# TSOC_GROVEY_ONE.net
KiCad netlist of a schematic drawn in EAGLE
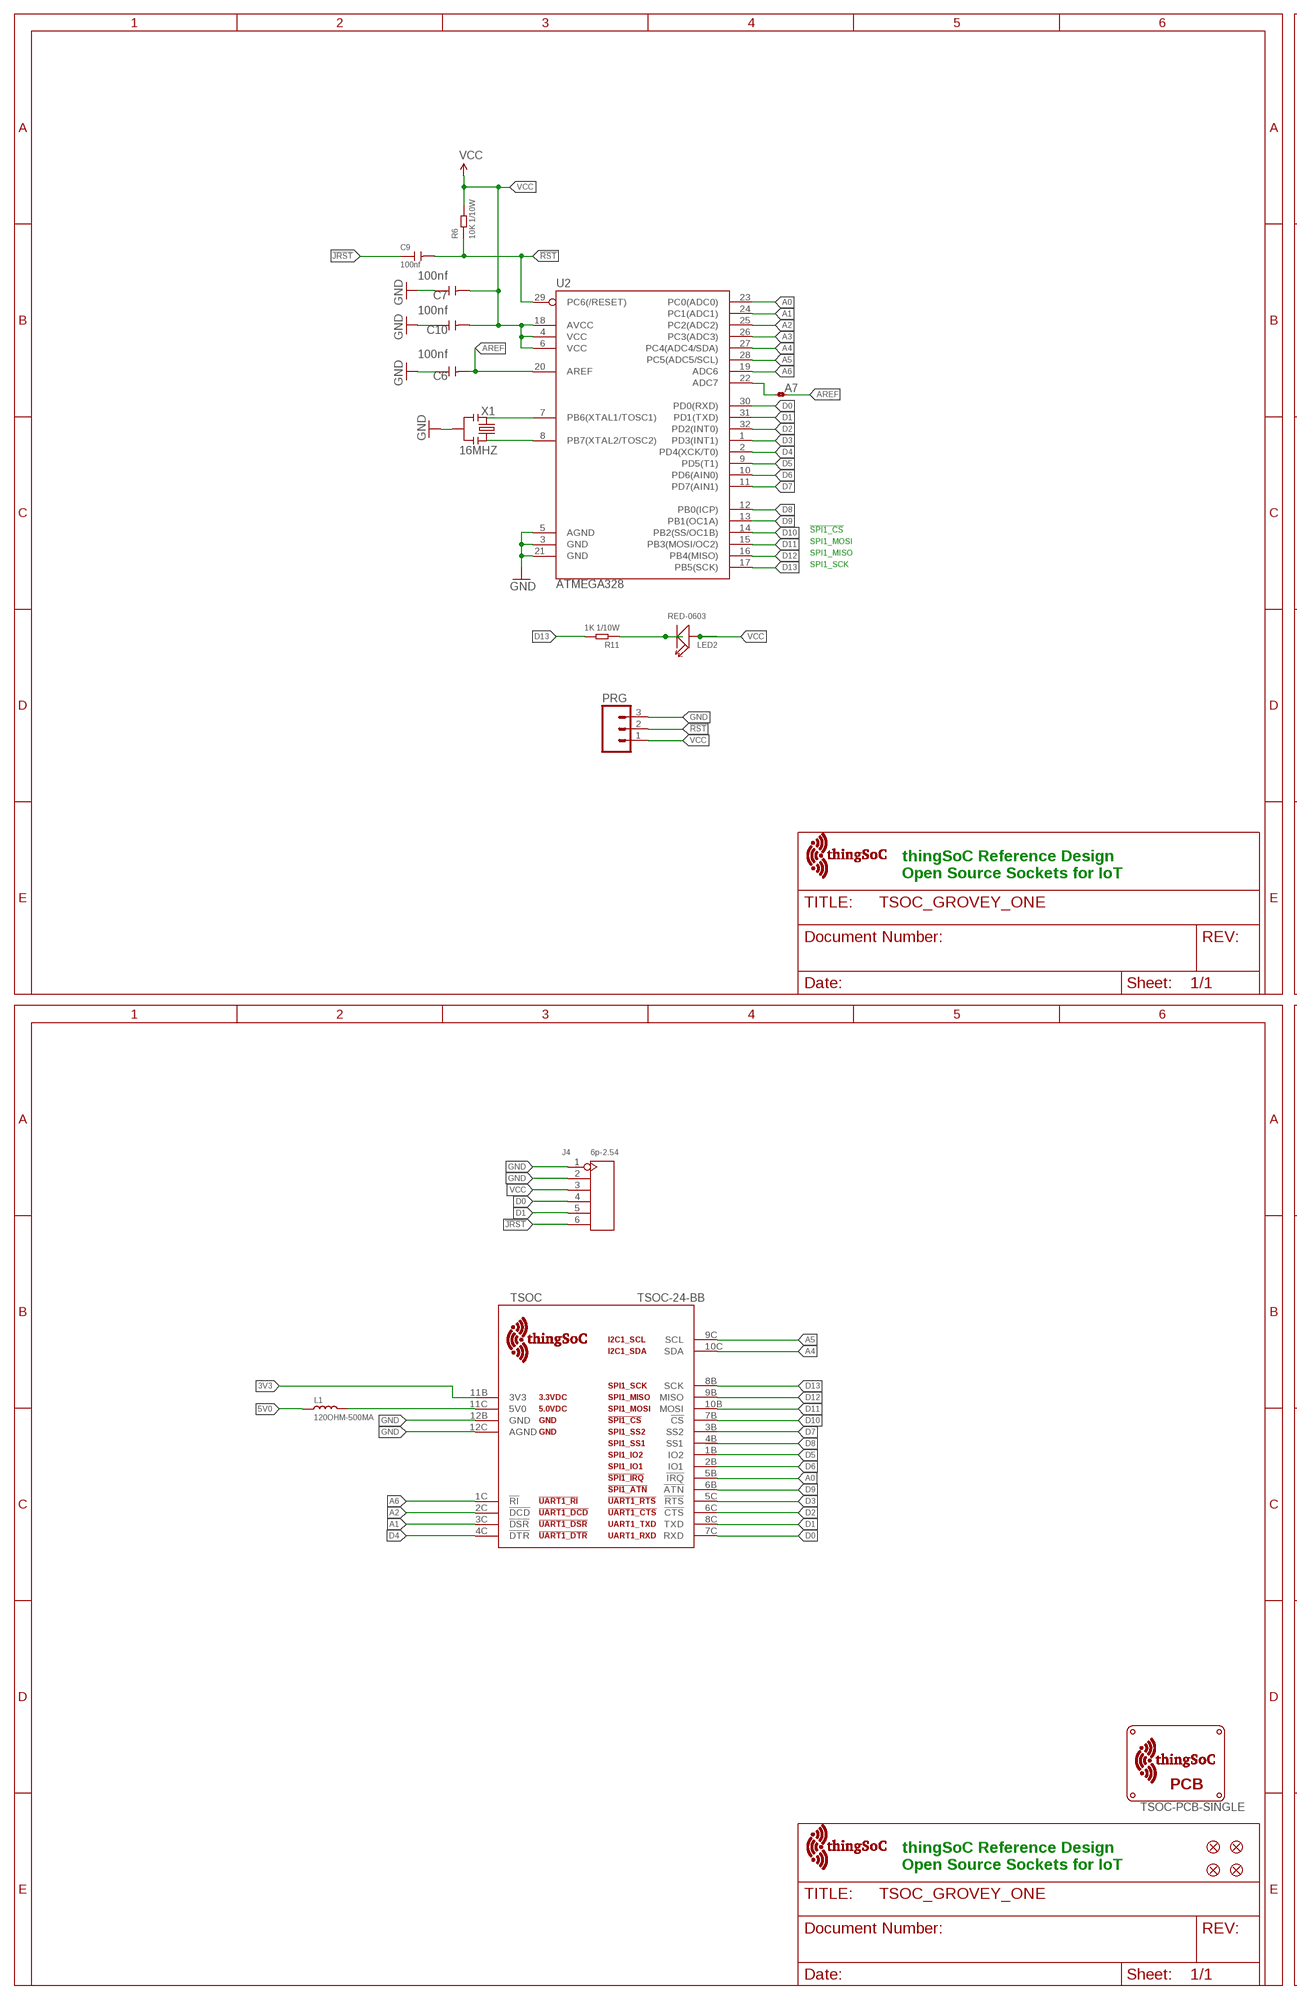
[diagram p0: schematic, sheet 1, part 1 of 2]
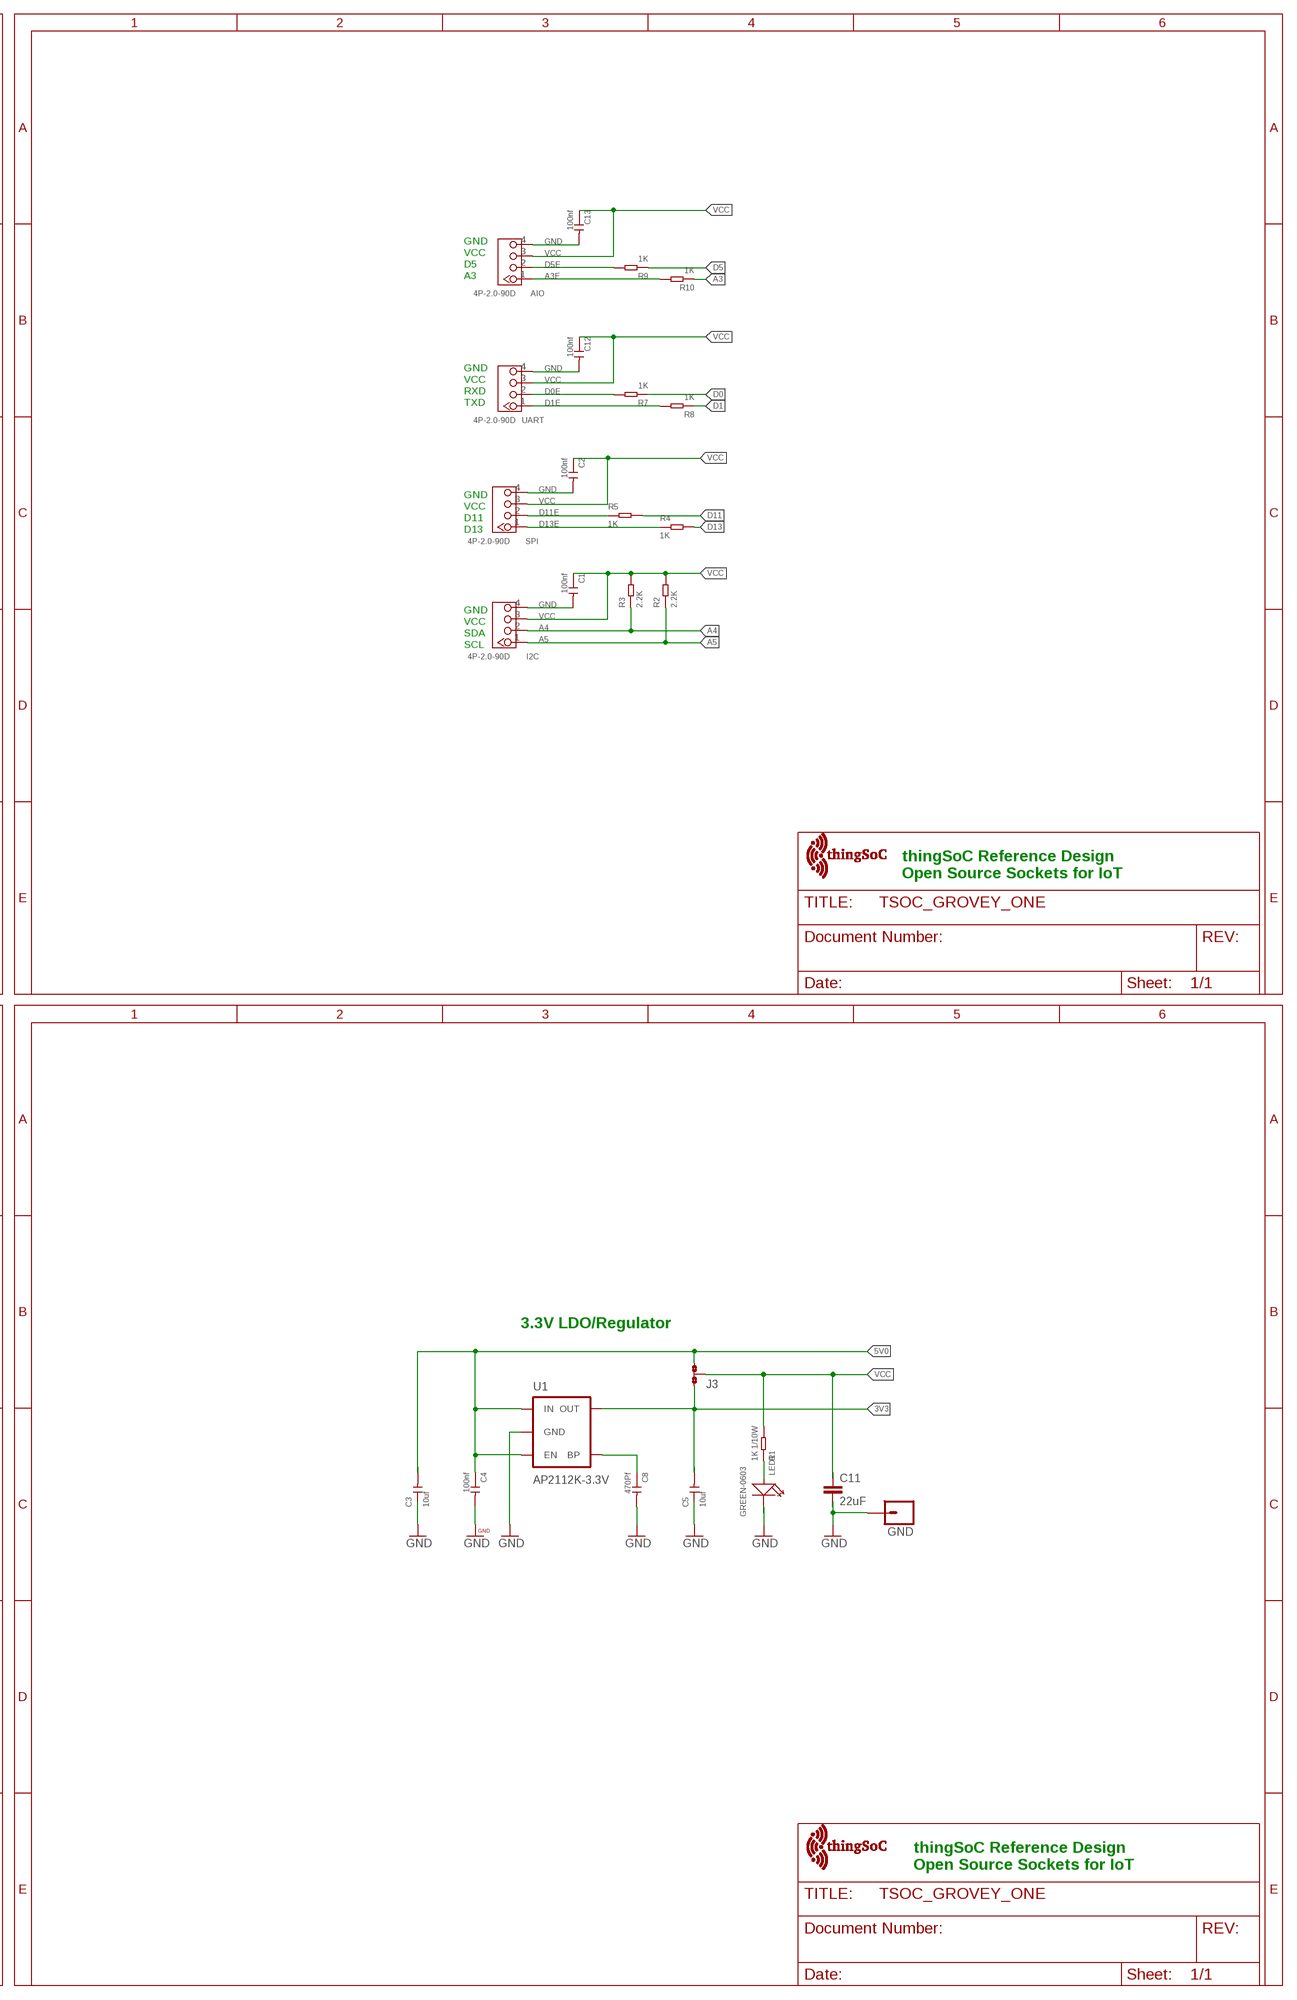
[diagram p1: schematic, sheet 1, part 2 of 2]

(export (version "E")
  (design (tool "Eeschema 10.0.6"))
  (components
    (comp (ref "$$U$1")
      (value "TSOC-PCB-SINGLE")
      (footprint "eagle-import:TSOC-BB-BRD-DIM")
      (libsource (lib "eagle-import") (part "TSOC-PCB-SINGLE"))
    )
    (comp (ref "A7")
      (value "JMP-2-NO")
      (footprint "eagle-import:JMP-2-NO")
      (libsource (lib "eagle-import") (part "JMP-2-NO"))
    )
    (comp (ref "AIO")
      (value "4P-2.0-90D")
      (footprint "eagle-import:HW4-2.0-90D")
      (libsource (lib "eagle-import") (part "GROVE-CONNECTOR-DIP-90D(4P-2.0)"))
    )
    (comp (ref "C1")
      (value "100nf")
      (footprint "eagle-import:C0603")
      (fields (field (name "MPN") "CC0603KRX7R9BB104"))
      (libsource (lib "eagle-import") (part "CERAMIC-100NF-50V-10%-X7R(0603)"))
    )
    (comp (ref "C2")
      (value "100nf")
      (footprint "eagle-import:C0603")
      (fields (field (name "MPN") "CC0603KRX7R9BB104"))
      (libsource (lib "eagle-import") (part "CERAMIC-100NF-50V-10%-X7R(0603)"))
    )
    (comp (ref "C3")
      (value "10uf")
      (footprint "eagle-import:C0603")
      (fields (field (name "MPN") "CC0603KRX5R6BB106"))
      (libsource (lib "eagle-import") (part "CERAMIC-10UF-10V-10%-X5R(0603)"))
    )
    (comp (ref "C4")
      (value "100nf")
      (footprint "eagle-import:C0603")
      (fields (field (name "MPN") "CC0603KRX7R9BB104"))
      (libsource (lib "eagle-import") (part "CERAMIC-100NF-50V-10%-X7R(0603)"))
    )
    (comp (ref "C5")
      (value "10uf")
      (footprint "eagle-import:C0603")
      (fields (field (name "MPN") "CC0603KRX5R6BB106"))
      (libsource (lib "eagle-import") (part "CERAMIC-10UF-10V-10%-X5R(0603)"))
    )
    (comp (ref "C6")
      (value "100nf")
      (footprint "eagle-import:C0603")
      (fields (field (name "MPN") "CC0603KRX7R9BB104"))
      (libsource (lib "eagle-import") (part "CERAMIC-100NF-50V-10%-X7R(0603)"))
    )
    (comp (ref "C7")
      (value "100nf")
      (footprint "eagle-import:C0603")
      (fields (field (name "MPN") "CC0603KRX7R9BB104"))
      (libsource (lib "eagle-import") (part "CERAMIC-100NF-50V-10%-X7R(0603)"))
    )
    (comp (ref "C8")
      (value "470Pf")
      (footprint "eagle-import:C0603")
      (fields (field (name "MPN") "CC0603KRX7R9BB104"))
      (libsource (lib "eagle-import") (part "CERAMIC-100NF-50V-10%-X7R(0603)"))
    )
    (comp (ref "C9")
      (value "100nf")
      (footprint "eagle-import:C0603")
      (fields (field (name "MPN") "CC0603KRX7R9BB104"))
      (libsource (lib "eagle-import") (part "CERAMIC-100NF-50V-10%-X7R(0603)"))
    )
    (comp (ref "C10")
      (value "100nf")
      (footprint "eagle-import:C0603")
      (fields (field (name "MPN") "CC0603KRX7R9BB104"))
      (libsource (lib "eagle-import") (part "CERAMIC-100NF-50V-10%-X7R(0603)"))
    )
    (comp (ref "C11")
      (value "22uF")
      (footprint "eagle-import:EIA-1206")
      (libsource (lib "eagle-import") (part "CAP-1206"))
    )
    (comp (ref "C12")
      (value "100nf")
      (footprint "eagle-import:C0603")
      (fields (field (name "MPN") "CC0603KRX7R9BB104"))
      (libsource (lib "eagle-import") (part "CERAMIC-100NF-50V-10%-X7R(0603)"))
    )
    (comp (ref "C13")
      (value "100nf")
      (footprint "eagle-import:C0603")
      (fields (field (name "MPN") "CC0603KRX7R9BB104"))
      (libsource (lib "eagle-import") (part "CERAMIC-100NF-50V-10%-X7R(0603)"))
    )
    (comp (ref "FID1")
      (value "FIDUCIALUFIDUCIAL")
      (footprint "eagle-import:MICRO-FIDUCIAL")
      (libsource (lib "eagle-import") (part "FIDUCIALUFIDUCIAL"))
    )
    (comp (ref "FID2")
      (value "FIDUCIALUFIDUCIAL")
      (footprint "eagle-import:MICRO-FIDUCIAL")
      (libsource (lib "eagle-import") (part "FIDUCIALUFIDUCIAL"))
    )
    (comp (ref "FID3")
      (value "FIDUCIALUFIDUCIAL")
      (footprint "eagle-import:MICRO-FIDUCIAL")
      (libsource (lib "eagle-import") (part "FIDUCIALUFIDUCIAL"))
    )
    (comp (ref "FID4")
      (value "FIDUCIALUFIDUCIAL")
      (footprint "eagle-import:MICRO-FIDUCIAL")
      (libsource (lib "eagle-import") (part "FIDUCIALUFIDUCIAL"))
    )
    (comp (ref "GND")
      (value "M01PTH")
      (footprint "eagle-import:1X01")
      (libsource (lib "eagle-import") (part "M01PTH"))
    )
    (comp (ref "I2C")
      (value "4P-2.0-90D")
      (footprint "eagle-import:HW4-2.0-90D")
      (libsource (lib "eagle-import") (part "GROVE-CONNECTOR-DIP-90D(4P-2.0)"))
    )
    (comp (ref "J3")
      (value "NO")
      (footprint "eagle-import:JMP-3-NO-PTH-2.54")
      (libsource (lib "eagle-import") (part "JMP-3-NO-PTH"))
    )
    (comp (ref "J4")
      (value "6p-2.54")
      (footprint "eagle-import:H6-2.54")
      (fields (field (name "MPN") "P125-1106A1BS116A1"))
      (libsource (lib "eagle-import") (part "DIP-BLACK-MALE-HEADER(6P-2.54)"))
    )
    (comp (ref "L1")
      (value "120OHM-500MA")
      (footprint "eagle-import:L0603")
      (fields (field (name "MPN") "BLM18AG121SN1D"))
      (libsource (lib "eagle-import") (part "SMD-FERRITE-CHIP-120-OHM-500MA(0603)"))
    )
    (comp (ref "LED1")
      (value "GREEN-0603")
      (footprint "eagle-import:LED-0603")
      (fields (field (name "MPN") "19-217-G7C-AN1P2-3T"))
      (libsource (lib "eagle-import") (part "SMD-LED-CLEAR-GREEN(0603)"))
    )
    (comp (ref "LED2")
      (value "RED-0603")
      (footprint "eagle-import:LED-0603")
      (fields (field (name "MPN") "19-217-G7C-AN1P2-3T"))
      (libsource (lib "eagle-import") (part "SMD-LED-CLEAR-GREEN(0603)"))
    )
    (comp (ref "PRG")
      (value "M03PTH")
      (footprint "eagle-import:1X03")
      (libsource (lib "eagle-import") (part "M03PTH"))
    )
    (comp (ref "R1")
      (value "1K 1/10W")
      (footprint "eagle-import:R0603")
      (fields (field (name "MPN") "RC0603JR-071KL"))
      (libsource (lib "eagle-import") (part "SMD-RES-1K-5%-1/10W(0603)"))
    )
    (comp (ref "R2")
      (value "2.2K")
      (footprint "eagle-import:R0603")
      (fields (field (name "MPN") "RC0603JR-072K2L"))
      (libsource (lib "eagle-import") (part "SMD-RES-2.2K-5%-1/10W(0603)"))
    )
    (comp (ref "R3")
      (value "2.2K")
      (footprint "eagle-import:R0603")
      (fields (field (name "MPN") "RC0603JR-072K2L"))
      (libsource (lib "eagle-import") (part "SMD-RES-2.2K-5%-1/10W(0603)"))
    )
    (comp (ref "R4")
      (value "1K")
      (footprint "eagle-import:R0603")
      (fields (field (name "MPN") "RC0603JR-072K2L"))
      (libsource (lib "eagle-import") (part "SMD-RES-2.2K-5%-1/10W(0603)"))
    )
    (comp (ref "R5")
      (value "1K")
      (footprint "eagle-import:R0603")
      (fields (field (name "MPN") "RC0603JR-072K2L"))
      (libsource (lib "eagle-import") (part "SMD-RES-2.2K-5%-1/10W(0603)"))
    )
    (comp (ref "R6")
      (value "10K 1/10W")
      (footprint "eagle-import:R0603")
      (fields (field (name "MPN") "RC0603JR-0710KL"))
      (libsource (lib "eagle-import") (part "SMD-RES-10K-5%-1/10W(0603)"))
    )
    (comp (ref "R7")
      (value "1K")
      (footprint "eagle-import:R0603")
      (fields (field (name "MPN") "RC0603JR-072K2L"))
      (libsource (lib "eagle-import") (part "SMD-RES-2.2K-5%-1/10W(0603)"))
    )
    (comp (ref "R8")
      (value "1K")
      (footprint "eagle-import:R0603")
      (fields (field (name "MPN") "RC0603JR-072K2L"))
      (libsource (lib "eagle-import") (part "SMD-RES-2.2K-5%-1/10W(0603)"))
    )
    (comp (ref "R9")
      (value "1K")
      (footprint "eagle-import:R0603")
      (fields (field (name "MPN") "RC0603JR-072K2L"))
      (libsource (lib "eagle-import") (part "SMD-RES-2.2K-5%-1/10W(0603)"))
    )
    (comp (ref "R10")
      (value "1K")
      (footprint "eagle-import:R0603")
      (fields (field (name "MPN") "RC0603JR-072K2L"))
      (libsource (lib "eagle-import") (part "SMD-RES-2.2K-5%-1/10W(0603)"))
    )
    (comp (ref "R11")
      (value "1K 1/10W")
      (footprint "eagle-import:R0603")
      (fields (field (name "MPN") "RC0603JR-071KL"))
      (libsource (lib "eagle-import") (part "SMD-RES-1K-5%-1/10W(0603)"))
    )
    (comp (ref "SPI")
      (value "4P-2.0-90D")
      (footprint "eagle-import:HW4-2.0-90D")
      (libsource (lib "eagle-import") (part "GROVE-CONNECTOR-DIP-90D(4P-2.0)"))
    )
    (comp (ref "TSOC")
      (value "TSOC-24-BB")
      (footprint "eagle-import:TSOC-BB-S24")
      (libsource (lib "eagle-import") (part "TSOC-24-BB"))
    )
    (comp (ref "U$1")
      (value "TSOC-LOGO-SMALL")
      (footprint "eagle-import:TSOC-LOGO-SML")
      (libsource (lib "eagle-import") (part "TSOC-LOGO-SMALL"))
    )
    (comp (ref "U$101")
      (value "TSOC-LOGO-SMALL")
      (footprint "eagle-import:TSOC-LOGO-SML")
      (libsource (lib "eagle-import") (part "TSOC-LOGO-SMALL"))
    )
    (comp (ref "U$102")
      (value "TSOC-LOGO-LRG")
      (footprint "eagle-import:TSOC-LOGO-LRG")
      (libsource (lib "eagle-import") (part "TSOC-LOGO-LRG"))
    )
    (comp (ref "U$103")
      (value "TSOC-LOGO-SMALL")
      (footprint "eagle-import:TSOC-LOGO-SML")
      (libsource (lib "eagle-import") (part "TSOC-LOGO-SMALL"))
    )
    (comp (ref "U1")
      (value "AP2112K-3.3V")
      (footprint "eagle-import:SOT23-5")
      (libsource (lib "eagle-import") (part "V_REG_LDOSMD"))
    )
    (comp (ref "U2")
      (value "ATMEGA328")
      (footprint "eagle-import:TQFP32-08")
      (libsource (lib "eagle-import") (part "ATMEGA168"))
    )
    (comp (ref "UART")
      (value "4P-2.0-90D")
      (footprint "eagle-import:HW4-2.0-90D")
      (libsource (lib "eagle-import") (part "GROVE-CONNECTOR-DIP-90D(4P-2.0)"))
    )
    (comp (ref "X1")
      (value "16MHZ")
      (footprint "eagle-import:X3-SMD-3.6X1.3X0.8MM")
      (fields (field (name "MPN") "CSTCE16M0V53-R0"))
      (libsource (lib "eagle-import") (part "SMD-RESONATOR-16MHZ-15PF-0.5%-40R(3P-3.2X1.3MM)"))
    )
  )
  (nets
    (net (code "1") (name "/A3E") (class "Default")
      (node (ref "AIO") (pin "1") (pinfunction "1_1") (pintype "bidirectional"))
      (node (ref "R10") (pin "2") (pinfunction "2_2") (pintype "passive"))
    )
    (net (code "2") (name "/D0E") (class "Default")
      (node (ref "R7") (pin "2") (pinfunction "2_2") (pintype "passive"))
      (node (ref "UART") (pin "2") (pinfunction "2_2") (pintype "bidirectional"))
    )
    (net (code "3") (name "/D1E") (class "Default")
      (node (ref "R8") (pin "2") (pinfunction "2_2") (pintype "passive"))
      (node (ref "UART") (pin "1") (pinfunction "1_1") (pintype "bidirectional"))
    )
    (net (code "4") (name "/D5E") (class "Default")
      (node (ref "AIO") (pin "2") (pinfunction "2_2") (pintype "bidirectional"))
      (node (ref "R9") (pin "2") (pinfunction "2_2") (pintype "passive"))
    )
    (net (code "5") (name "/D11E") (class "Default")
      (node (ref "R5") (pin "1") (pinfunction "1_1") (pintype "passive"))
      (node (ref "SPI") (pin "2") (pinfunction "2_2") (pintype "bidirectional"))
    )
    (net (code "6") (name "/D13E") (class "Default")
      (node (ref "R4") (pin "1") (pinfunction "1_1") (pintype "passive"))
      (node (ref "SPI") (pin "1") (pinfunction "1_1") (pintype "bidirectional"))
    )
    (net (code "7") (name "/~{JRST}") (class "Default")
      (node (ref "C9") (pin "1") (pinfunction "1_1") (pintype "passive"))
      (node (ref "J4") (pin "6") (pinfunction "6_6") (pintype "bidirectional"))
    )
    (net (code "8") (name "/~{RST}") (class "Default")
      (node (ref "C9") (pin "2") (pinfunction "2_2") (pintype "passive"))
      (node (ref "PRG") (pin "2") (pinfunction "2_2") (pintype "passive"))
      (node (ref "R6") (pin "1") (pinfunction "1_1") (pintype "passive"))
      (node (ref "U2") (pin "29") (pinfunction "PC6(/RESET)_29") (pintype "bidirectional"))
    )
    (net (code "9") (name "3V3") (class "Default")
      (node (ref "C5") (pin "2") (pinfunction "2_2") (pintype "passive"))
      (node (ref "J3") (pin "1") (pinfunction "1_1") (pintype "passive"))
      (node (ref "TSOC") (pin "11B") (pinfunction "3V3_11B") (pintype "bidirectional"))
      (node (ref "U1") (pin "5") (pinfunction "OUT_5") (pintype "passive"))
    )
    (net (code "10") (name "5V0") (class "Default")
      (node (ref "C3") (pin "2") (pinfunction "2_2") (pintype "passive"))
      (node (ref "C4") (pin "1") (pinfunction "1_1") (pintype "passive"))
      (node (ref "J3") (pin "3") (pinfunction "3_3") (pintype "passive"))
      (node (ref "L1") (pin "1") (pinfunction "1_1") (pintype "passive"))
      (node (ref "U1") (pin "1") (pinfunction "IN_1") (pintype "input"))
      (node (ref "U1") (pin "3") (pinfunction "EN_3") (pintype "input"))
    )
    (net (code "11") (name "A0") (class "Default")
      (node (ref "TSOC") (pin "5B") (pinfunction "~{IRQ}_5B") (pintype "bidirectional"))
      (node (ref "U2") (pin "23") (pinfunction "PC0(ADC0)_23") (pintype "bidirectional"))
    )
    (net (code "12") (name "A1") (class "Default")
      (node (ref "TSOC") (pin "3C") (pinfunction "~{DSR}_3C") (pintype "bidirectional"))
      (node (ref "U2") (pin "24") (pinfunction "PC1(ADC1)_24") (pintype "bidirectional"))
    )
    (net (code "13") (name "A2") (class "Default")
      (node (ref "TSOC") (pin "2C") (pinfunction "~{DCD}_2C") (pintype "bidirectional"))
      (node (ref "U2") (pin "25") (pinfunction "PC2(ADC2)_25") (pintype "bidirectional"))
    )
    (net (code "14") (name "A3") (class "Default")
      (node (ref "R10") (pin "1") (pinfunction "1_1") (pintype "passive"))
      (node (ref "U2") (pin "26") (pinfunction "PC3(ADC3)_26") (pintype "bidirectional"))
    )
    (net (code "15") (name "A4") (class "Default")
      (node (ref "I2C") (pin "2") (pinfunction "2_2") (pintype "bidirectional"))
      (node (ref "R3") (pin "1") (pinfunction "1_1") (pintype "passive"))
      (node (ref "TSOC") (pin "10C") (pinfunction "SDA_10C") (pintype "bidirectional"))
      (node (ref "U2") (pin "27") (pinfunction "PC4(ADC4/SDA)_27") (pintype "bidirectional"))
    )
    (net (code "16") (name "A5") (class "Default")
      (node (ref "I2C") (pin "1") (pinfunction "1_1") (pintype "bidirectional"))
      (node (ref "R2") (pin "1") (pinfunction "1_1") (pintype "passive"))
      (node (ref "TSOC") (pin "9C") (pinfunction "SCL_9C") (pintype "bidirectional"))
      (node (ref "U2") (pin "28") (pinfunction "PC5(ADC5/SCL)_28") (pintype "bidirectional"))
    )
    (net (code "17") (name "A6") (class "Default")
      (node (ref "TSOC") (pin "1C") (pinfunction "~{RI}_1C") (pintype "bidirectional"))
      (node (ref "U2") (pin "19") (pinfunction "ADC6_19") (pintype "bidirectional"))
    )
    (net (code "18") (name "AREF") (class "Default")
      (node (ref "A7") (pin "2") (pinfunction "2_2") (pintype "passive"))
      (node (ref "C6") (pin "2") (pinfunction "2_2") (pintype "passive"))
      (node (ref "U2") (pin "20") (pinfunction "AREF_20") (pintype "bidirectional"))
    )
    (net (code "19") (name "D0") (class "Default")
      (node (ref "J4") (pin "4") (pinfunction "4_4") (pintype "bidirectional"))
      (node (ref "R7") (pin "1") (pinfunction "1_1") (pintype "passive"))
      (node (ref "TSOC") (pin "7C") (pinfunction "RXD_7C") (pintype "bidirectional"))
      (node (ref "U2") (pin "30") (pinfunction "PD0(RXD)_30") (pintype "bidirectional"))
    )
    (net (code "20") (name "D1") (class "Default")
      (node (ref "J4") (pin "5") (pinfunction "5_5") (pintype "bidirectional"))
      (node (ref "R8") (pin "1") (pinfunction "1_1") (pintype "passive"))
      (node (ref "TSOC") (pin "8C") (pinfunction "TXD_8C") (pintype "bidirectional"))
      (node (ref "U2") (pin "31") (pinfunction "PD1(TXD)_31") (pintype "bidirectional"))
    )
    (net (code "21") (name "D2") (class "Default")
      (node (ref "TSOC") (pin "6C") (pinfunction "~{CTS}_6C") (pintype "bidirectional"))
      (node (ref "U2") (pin "32") (pinfunction "PD2(INT0)_32") (pintype "bidirectional"))
    )
    (net (code "22") (name "D3") (class "Default")
      (node (ref "TSOC") (pin "5C") (pinfunction "~{RTS}_5C") (pintype "bidirectional"))
      (node (ref "U2") (pin "1") (pinfunction "PD3(INT1)_1") (pintype "bidirectional"))
    )
    (net (code "23") (name "D4") (class "Default")
      (node (ref "TSOC") (pin "4C") (pinfunction "~{DTR}_4C") (pintype "bidirectional"))
      (node (ref "U2") (pin "2") (pinfunction "PD4(XCK/T0)_2") (pintype "bidirectional"))
    )
    (net (code "24") (name "D5") (class "Default")
      (node (ref "R9") (pin "1") (pinfunction "1_1") (pintype "passive"))
      (node (ref "TSOC") (pin "1B") (pinfunction "IO2_1B") (pintype "bidirectional"))
      (node (ref "U2") (pin "9") (pinfunction "PD5(T1)_9") (pintype "bidirectional"))
    )
    (net (code "25") (name "D6") (class "Default")
      (node (ref "TSOC") (pin "2B") (pinfunction "IO1_2B") (pintype "bidirectional"))
      (node (ref "U2") (pin "10") (pinfunction "PD6(AIN0)_10") (pintype "bidirectional"))
    )
    (net (code "26") (name "D7") (class "Default")
      (node (ref "TSOC") (pin "3B") (pinfunction "SS2_3B") (pintype "bidirectional"))
      (node (ref "U2") (pin "11") (pinfunction "PD7(AIN1)_11") (pintype "bidirectional"))
    )
    (net (code "27") (name "D8") (class "Default")
      (node (ref "TSOC") (pin "4B") (pinfunction "SS1_4B") (pintype "bidirectional"))
      (node (ref "U2") (pin "12") (pinfunction "PB0(ICP)_12") (pintype "bidirectional"))
    )
    (net (code "28") (name "D9") (class "Default")
      (node (ref "TSOC") (pin "6B") (pinfunction "~{ATN}_6B") (pintype "bidirectional"))
      (node (ref "U2") (pin "13") (pinfunction "PB1(OC1A)_13") (pintype "bidirectional"))
    )
    (net (code "29") (name "D10") (class "Default")
      (node (ref "TSOC") (pin "7B") (pinfunction "~{CS}_7B") (pintype "bidirectional"))
      (node (ref "U2") (pin "14") (pinfunction "PB2(SS/OC1B)_14") (pintype "bidirectional"))
    )
    (net (code "30") (name "D11") (class "Default")
      (node (ref "R5") (pin "2") (pinfunction "2_2") (pintype "passive"))
      (node (ref "TSOC") (pin "10B") (pinfunction "MOSI_10B") (pintype "bidirectional"))
      (node (ref "U2") (pin "15") (pinfunction "PB3(MOSI/OC2)_15") (pintype "bidirectional"))
    )
    (net (code "31") (name "D12") (class "Default")
      (node (ref "TSOC") (pin "9B") (pinfunction "MISO_9B") (pintype "bidirectional"))
      (node (ref "U2") (pin "16") (pinfunction "PB4(MISO)_16") (pintype "bidirectional"))
    )
    (net (code "32") (name "D13") (class "Default")
      (node (ref "R11") (pin "2") (pinfunction "2_2") (pintype "passive"))
      (node (ref "R4") (pin "2") (pinfunction "2_2") (pintype "passive"))
      (node (ref "TSOC") (pin "8B") (pinfunction "SCK_8B") (pintype "bidirectional"))
      (node (ref "U2") (pin "17") (pinfunction "PB5(SCK)_17") (pintype "bidirectional"))
    )
    (net (code "33") (name "GND") (class "Default")
      (node (ref "AIO") (pin "4") (pinfunction "4_4") (pintype "bidirectional"))
      (node (ref "C1") (pin "2") (pinfunction "2_2") (pintype "passive"))
      (node (ref "C10") (pin "1") (pinfunction "1_1") (pintype "passive"))
      (node (ref "C11") (pin "2") (pinfunction "2_2") (pintype "passive"))
      (node (ref "C12") (pin "2") (pinfunction "2_2") (pintype "passive"))
      (node (ref "C13") (pin "2") (pinfunction "2_2") (pintype "passive"))
      (node (ref "C2") (pin "2") (pinfunction "2_2") (pintype "passive"))
      (node (ref "C3") (pin "1") (pinfunction "1_1") (pintype "passive"))
      (node (ref "C4") (pin "2") (pinfunction "2_2") (pintype "passive"))
      (node (ref "C5") (pin "1") (pinfunction "1_1") (pintype "passive"))
      (node (ref "C6") (pin "1") (pinfunction "1_1") (pintype "passive"))
      (node (ref "C7") (pin "1") (pinfunction "1_1") (pintype "passive"))
      (node (ref "C8") (pin "2") (pinfunction "2_2") (pintype "passive"))
      (node (ref "GND") (pin "1") (pinfunction "1_1") (pintype "passive"))
      (node (ref "I2C") (pin "4") (pinfunction "4_4") (pintype "bidirectional"))
      (node (ref "J4") (pin "1") (pinfunction "1_1") (pintype "bidirectional"))
      (node (ref "J4") (pin "2") (pinfunction "2_2") (pintype "bidirectional"))
      (node (ref "LED1") (pin "-") (pinfunction "-_-") (pintype "passive"))
      (node (ref "PRG") (pin "3") (pinfunction "3_3") (pintype "passive"))
      (node (ref "SPI") (pin "4") (pinfunction "4_4") (pintype "bidirectional"))
      (node (ref "TSOC") (pin "12B") (pinfunction "GND_12B") (pintype "bidirectional"))
      (node (ref "TSOC") (pin "12C") (pinfunction "AGND_12C") (pintype "bidirectional"))
      (node (ref "U1") (pin "2") (pinfunction "GND_2") (pintype "input"))
      (node (ref "U2") (pin "21") (pinfunction "GND_21") (pintype "bidirectional"))
      (node (ref "U2") (pin "3") (pinfunction "GND_3") (pintype "bidirectional"))
      (node (ref "U2") (pin "5") (pinfunction "AGND_5") (pintype "bidirectional"))
      (node (ref "UART") (pin "4") (pinfunction "4_4") (pintype "bidirectional"))
      (node (ref "X1") (pin "2") (pinfunction "2_2") (pintype "passive"))
    )
    (net (code "34") (name "Net-(LED1-Pad+)") (class "Default")
      (node (ref "LED1") (pin "+") (pinfunction "+_+") (pintype "passive"))
      (node (ref "R1") (pin "1") (pinfunction "1_1") (pintype "passive"))
    )
    (net (code "35") (name "Net-(LED2-Pad-)") (class "Default")
      (node (ref "LED2") (pin "-") (pinfunction "-_-") (pintype "passive"))
      (node (ref "R11") (pin "1") (pinfunction "1_1") (pintype "passive"))
    )
    (net (code "36") (name "Net-(TSOC-5V0)") (class "Default")
      (node (ref "L1") (pin "2") (pinfunction "2_2") (pintype "passive"))
      (node (ref "TSOC") (pin "11C") (pinfunction "5V0_11C") (pintype "bidirectional"))
    )
    (net (code "37") (name "Net-(U1-BP)") (class "Default")
      (node (ref "C8") (pin "1") (pinfunction "1_1") (pintype "passive"))
      (node (ref "U1") (pin "4") (pinfunction "BP_4") (pintype "input"))
    )
    (net (code "38") (name "Net-(U2-ADC7)") (class "Default")
      (node (ref "A7") (pin "1") (pinfunction "1_1") (pintype "passive"))
      (node (ref "U2") (pin "22") (pinfunction "ADC7_22") (pintype "bidirectional"))
    )
    (net (code "39") (name "Net-(U2-PB6(XTAL1{slash}TOSC1))") (class "Default")
      (node (ref "U2") (pin "7") (pinfunction "PB6(XTAL1/TOSC1)_7") (pintype "bidirectional"))
      (node (ref "X1") (pin "3") (pinfunction "3_3") (pintype "passive"))
    )
    (net (code "40") (name "Net-(U2-PB7(XTAL2{slash}TOSC2))") (class "Default")
      (node (ref "U2") (pin "8") (pinfunction "PB7(XTAL2/TOSC2)_8") (pintype "bidirectional"))
      (node (ref "X1") (pin "1") (pinfunction "1_1") (pintype "passive"))
    )
    (net (code "41") (name "VCC") (class "Default")
      (node (ref "AIO") (pin "3") (pinfunction "3_3") (pintype "bidirectional"))
      (node (ref "C1") (pin "1") (pinfunction "1_1") (pintype "passive"))
      (node (ref "C10") (pin "2") (pinfunction "2_2") (pintype "passive"))
      (node (ref "C11") (pin "1") (pinfunction "1_1") (pintype "passive"))
      (node (ref "C12") (pin "1") (pinfunction "1_1") (pintype "passive"))
      (node (ref "C13") (pin "1") (pinfunction "1_1") (pintype "passive"))
      (node (ref "C2") (pin "1") (pinfunction "1_1") (pintype "passive"))
      (node (ref "C7") (pin "2") (pinfunction "2_2") (pintype "passive"))
      (node (ref "I2C") (pin "3") (pinfunction "3_3") (pintype "bidirectional"))
      (node (ref "J3") (pin "2") (pinfunction "2_2") (pintype "passive"))
      (node (ref "J4") (pin "3") (pinfunction "3_3") (pintype "bidirectional"))
      (node (ref "LED2") (pin "+") (pinfunction "+_+") (pintype "passive"))
      (node (ref "PRG") (pin "1") (pinfunction "1_1") (pintype "passive"))
      (node (ref "R1") (pin "2") (pinfunction "2_2") (pintype "passive"))
      (node (ref "R2") (pin "2") (pinfunction "2_2") (pintype "passive"))
      (node (ref "R3") (pin "2") (pinfunction "2_2") (pintype "passive"))
      (node (ref "R6") (pin "2") (pinfunction "2_2") (pintype "passive"))
      (node (ref "SPI") (pin "3") (pinfunction "3_3") (pintype "bidirectional"))
      (node (ref "U2") (pin "18") (pinfunction "AVCC_18") (pintype "bidirectional"))
      (node (ref "U2") (pin "4") (pinfunction "VCC_4") (pintype "bidirectional"))
      (node (ref "U2") (pin "6") (pinfunction "VCC_6") (pintype "bidirectional"))
      (node (ref "UART") (pin "3") (pinfunction "3_3") (pintype "bidirectional"))
    )
  )
)
